# LPCB228_-_TOP.net
KiCad netlist of a schematic drawn in Altium Designer
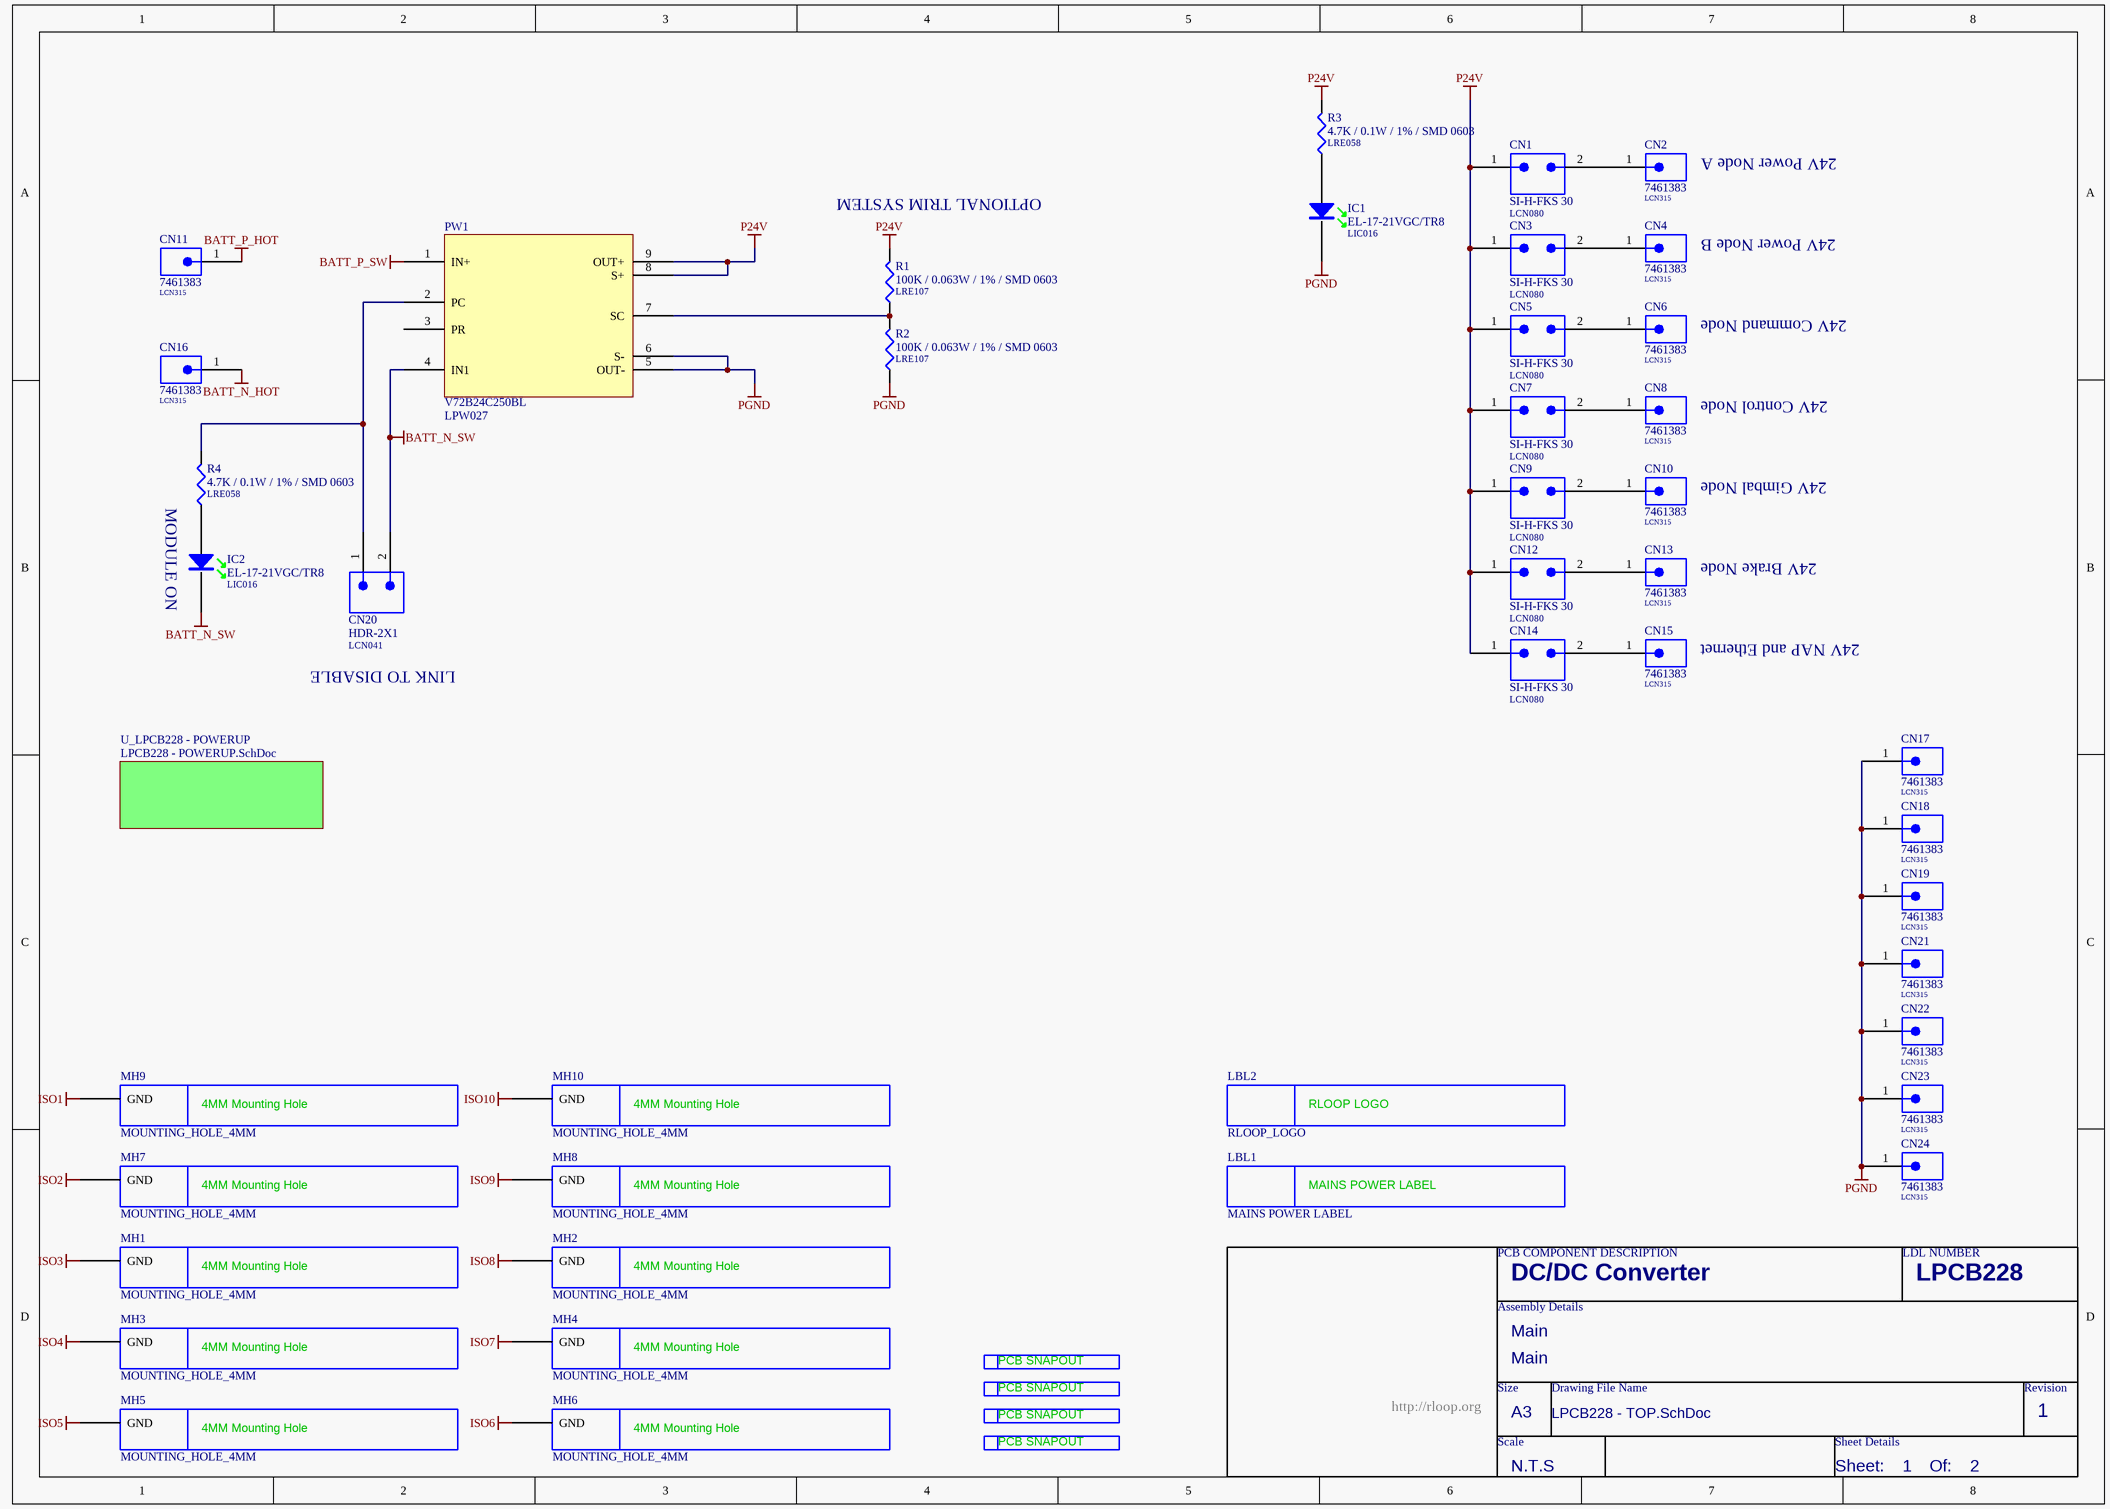
[diagram p0: LPCB228 - TOP.SchDoc]

(export (version "E")
  (design (tool "Eeschema 10.0.6"))
  (components
    (comp (ref "CN1")
      (value "SI-H-FKS 30")
      (footprint "SI-H-FKS-30")
      (description "Connector, Blade Fuse Holder, 5mm Terminals, 30A Max, PTH")
      (fields (field (name "LDL_NUMBER") "LCN080"))
      (libsource (lib "LDL_Connectors") (part "SI-H-FKS 30"))
    )
    (comp (ref "CN2")
      (value "7461383")
      (footprint "7461383")
      (description "Terminal, Bush with M5 Shank")
      (fields (field (name "LDL_NUMBER") "LCN315"))
      (libsource (lib "LDL_Connectors") (part "7461383"))
    )
    (comp (ref "CN3")
      (value "SI-H-FKS 30")
      (footprint "SI-H-FKS-30")
      (description "Connector, Blade Fuse Holder, 5mm Terminals, 30A Max, PTH")
      (fields (field (name "LDL_NUMBER") "LCN080"))
      (libsource (lib "LDL_Connectors") (part "SI-H-FKS 30"))
    )
    (comp (ref "CN4")
      (value "7461383")
      (footprint "7461383")
      (description "Terminal, Bush with M5 Shank")
      (fields (field (name "LDL_NUMBER") "LCN315"))
      (libsource (lib "LDL_Connectors") (part "7461383"))
    )
    (comp (ref "CN5")
      (value "SI-H-FKS 30")
      (footprint "SI-H-FKS-30")
      (description "Connector, Blade Fuse Holder, 5mm Terminals, 30A Max, PTH")
      (fields (field (name "LDL_NUMBER") "LCN080"))
      (libsource (lib "LDL_Connectors") (part "SI-H-FKS 30"))
    )
    (comp (ref "CN6")
      (value "7461383")
      (footprint "7461383")
      (description "Terminal, Bush with M5 Shank")
      (fields (field (name "LDL_NUMBER") "LCN315"))
      (libsource (lib "LDL_Connectors") (part "7461383"))
    )
    (comp (ref "CN7")
      (value "SI-H-FKS 30")
      (footprint "SI-H-FKS-30")
      (description "Connector, Blade Fuse Holder, 5mm Terminals, 30A Max, PTH")
      (fields (field (name "LDL_NUMBER") "LCN080"))
      (libsource (lib "LDL_Connectors") (part "SI-H-FKS 30"))
    )
    (comp (ref "CN8")
      (value "7461383")
      (footprint "7461383")
      (description "Terminal, Bush with M5 Shank")
      (fields (field (name "LDL_NUMBER") "LCN315"))
      (libsource (lib "LDL_Connectors") (part "7461383"))
    )
    (comp (ref "CN9")
      (value "SI-H-FKS 30")
      (footprint "SI-H-FKS-30")
      (description "Connector, Blade Fuse Holder, 5mm Terminals, 30A Max, PTH")
      (fields (field (name "LDL_NUMBER") "LCN080"))
      (libsource (lib "LDL_Connectors") (part "SI-H-FKS 30"))
    )
    (comp (ref "CN10")
      (value "7461383")
      (footprint "7461383")
      (description "Terminal, Bush with M5 Shank")
      (fields (field (name "LDL_NUMBER") "LCN315"))
      (libsource (lib "LDL_Connectors") (part "7461383"))
    )
    (comp (ref "CN11")
      (value "7461383")
      (footprint "7461383")
      (description "Terminal, Bush with M5 Shank")
      (fields (field (name "LDL_NUMBER") "LCN315"))
      (libsource (lib "LDL_Connectors") (part "7461383"))
    )
    (comp (ref "CN12")
      (value "SI-H-FKS 30")
      (footprint "SI-H-FKS-30")
      (description "Connector, Blade Fuse Holder, 5mm Terminals, 30A Max, PTH")
      (fields (field (name "LDL_NUMBER") "LCN080"))
      (libsource (lib "LDL_Connectors") (part "SI-H-FKS 30"))
    )
    (comp (ref "CN13")
      (value "7461383")
      (footprint "7461383")
      (description "Terminal, Bush with M5 Shank")
      (fields (field (name "LDL_NUMBER") "LCN315"))
      (libsource (lib "LDL_Connectors") (part "7461383"))
    )
    (comp (ref "CN14")
      (value "SI-H-FKS 30")
      (footprint "SI-H-FKS-30")
      (description "Connector, Blade Fuse Holder, 5mm Terminals, 30A Max, PTH")
      (fields (field (name "LDL_NUMBER") "LCN080"))
      (libsource (lib "LDL_Connectors") (part "SI-H-FKS 30"))
    )
    (comp (ref "CN15")
      (value "7461383")
      (footprint "7461383")
      (description "Terminal, Bush with M5 Shank")
      (fields (field (name "LDL_NUMBER") "LCN315"))
      (libsource (lib "LDL_Connectors") (part "7461383"))
    )
    (comp (ref "CN16")
      (value "7461383")
      (footprint "7461383")
      (description "Terminal, Bush with M5 Shank")
      (fields (field (name "LDL_NUMBER") "LCN315"))
      (libsource (lib "LDL_Connectors") (part "7461383"))
    )
    (comp (ref "CN17")
      (value "7461383")
      (footprint "7461383")
      (description "Terminal, Bush with M5 Shank")
      (fields (field (name "LDL_NUMBER") "LCN315"))
      (libsource (lib "LDL_Connectors") (part "7461383"))
    )
    (comp (ref "CN18")
      (value "7461383")
      (footprint "7461383")
      (description "Terminal, Bush with M5 Shank")
      (fields (field (name "LDL_NUMBER") "LCN315"))
      (libsource (lib "LDL_Connectors") (part "7461383"))
    )
    (comp (ref "CN19")
      (value "7461383")
      (footprint "7461383")
      (description "Terminal, Bush with M5 Shank")
      (fields (field (name "LDL_NUMBER") "LCN315"))
      (libsource (lib "LDL_Connectors") (part "7461383"))
    )
    (comp (ref "CN20")
      (value "HDR-2X1")
      (footprint "HDR-2X1")
      (description "Header, 2.54mm (0.1in), 2 Pins x 1 Row (40 Per Row In Strip)")
      (fields (field (name "LDL_NUMBER") "LCN041"))
      (libsource (lib "LDL_Connectors") (part "HDR-2X1"))
    )
    (comp (ref "CN21")
      (value "7461383")
      (footprint "7461383")
      (description "Terminal, Bush with M5 Shank")
      (fields (field (name "LDL_NUMBER") "LCN315"))
      (libsource (lib "LDL_Connectors") (part "7461383"))
    )
    (comp (ref "CN22")
      (value "7461383")
      (footprint "7461383")
      (description "Terminal, Bush with M5 Shank")
      (fields (field (name "LDL_NUMBER") "LCN315"))
      (libsource (lib "LDL_Connectors") (part "7461383"))
    )
    (comp (ref "CN23")
      (value "7461383")
      (footprint "7461383")
      (description "Terminal, Bush with M5 Shank")
      (fields (field (name "LDL_NUMBER") "LCN315"))
      (libsource (lib "LDL_Connectors") (part "7461383"))
    )
    (comp (ref "CN24")
      (value "7461383")
      (footprint "7461383")
      (description "Terminal, Bush with M5 Shank")
      (fields (field (name "LDL_NUMBER") "LCN315"))
      (libsource (lib "LDL_Connectors") (part "7461383"))
    )
    (comp (ref "IC1")
      (value "EL-17-21VGC/TR8")
      (footprint "CR2012-0805-LED")
      (description "LED, SMD, 0805 Green [LIC016]")
      (fields (field (name "LDL_NUMBER") "LIC016"))
      (libsource (lib "LDL_Semiconductors") (part "EL-17-21VGC/TR8"))
    )
    (comp (ref "IC2")
      (value "EL-17-21VGC/TR8")
      (footprint "CR2012-0805-LED")
      (description "LED, SMD, 0805 Green [LIC016]")
      (fields (field (name "LDL_NUMBER") "LIC016"))
      (libsource (lib "LDL_Semiconductors") (part "EL-17-21VGC/TR8"))
    )
    (comp (ref "LBL1")
      (value "MAINS POWER LABEL")
      (footprint "MAINS POWER LABEL")
      (libsource (lib "LDL_Mechanical") (part "MAINS POWER LABEL"))
    )
    (comp (ref "LBL2")
      (value "RLOOP_LOGO")
      (footprint "RLOOP_LOGO")
      (libsource (lib "LDL_Mechanical") (part "RLOOP_LOGO"))
    )
    (comp (ref "MH1")
      (value "MOUNTING_HOLE_4MM")
      (footprint "MOUNTING_HOLE_4MM")
      (description "4MM Mouting Hole")
      (libsource (lib "LDL_Mechanical") (part "MOUNTING_HOLE_4MM"))
    )
    (comp (ref "MH2")
      (value "MOUNTING_HOLE_4MM")
      (footprint "MOUNTING_HOLE_4MM")
      (description "4MM Mouting Hole")
      (libsource (lib "LDL_Mechanical") (part "MOUNTING_HOLE_4MM"))
    )
    (comp (ref "MH3")
      (value "MOUNTING_HOLE_4MM")
      (footprint "MOUNTING_HOLE_4MM")
      (description "4MM Mouting Hole")
      (libsource (lib "LDL_Mechanical") (part "MOUNTING_HOLE_4MM"))
    )
    (comp (ref "MH4")
      (value "MOUNTING_HOLE_4MM")
      (footprint "MOUNTING_HOLE_4MM")
      (description "4MM Mouting Hole")
      (libsource (lib "LDL_Mechanical") (part "MOUNTING_HOLE_4MM"))
    )
    (comp (ref "MH5")
      (value "MOUNTING_HOLE_4MM")
      (footprint "MOUNTING_HOLE_4MM")
      (description "4MM Mouting Hole")
      (libsource (lib "LDL_Mechanical") (part "MOUNTING_HOLE_4MM"))
    )
    (comp (ref "MH6")
      (value "MOUNTING_HOLE_4MM")
      (footprint "MOUNTING_HOLE_4MM")
      (description "4MM Mouting Hole")
      (libsource (lib "LDL_Mechanical") (part "MOUNTING_HOLE_4MM"))
    )
    (comp (ref "MH7")
      (value "MOUNTING_HOLE_4MM")
      (footprint "MOUNTING_HOLE_4MM")
      (description "4MM Mouting Hole")
      (libsource (lib "LDL_Mechanical") (part "MOUNTING_HOLE_4MM"))
    )
    (comp (ref "MH8")
      (value "MOUNTING_HOLE_4MM")
      (footprint "MOUNTING_HOLE_4MM")
      (description "4MM Mouting Hole")
      (libsource (lib "LDL_Mechanical") (part "MOUNTING_HOLE_4MM"))
    )
    (comp (ref "MH9")
      (value "MOUNTING_HOLE_4MM")
      (footprint "MOUNTING_HOLE_4MM")
      (description "4MM Mouting Hole")
      (libsource (lib "LDL_Mechanical") (part "MOUNTING_HOLE_4MM"))
    )
    (comp (ref "MH10")
      (value "MOUNTING_HOLE_4MM")
      (footprint "MOUNTING_HOLE_4MM")
      (description "4MM Mouting Hole")
      (libsource (lib "LDL_Mechanical") (part "MOUNTING_HOLE_4MM"))
    )
    (comp (ref "PW1")
      (value "V72B24C250BL")
      (footprint "FASTRAK_MINI_ONBOARD_MOUNT")
      (description "DC-DC Converter, 43-110VIN, 24V, 10A")
      (fields (field (name "LDL_NUMBER") "LPW027"))
      (libsource (lib "LDL_Power") (part "V72B24C250BL"))
    )
    (comp (ref "R1")
      (value "100K / 0.063W / 1% / SMD 0603")
      (footprint "LFP020__CR1608-0603-IPC7351_B")
      (description "Resistor, Ceramic Chip, 100K0, 0.063W, 1%, SMD 0603 [LRE107]")
      (fields (field (name "LDL_NUMBER") "LRE107"))
      (libsource (lib "LDL_Resistors") (part "100K / 0.063W / 1% / SMD 0603"))
    )
    (comp (ref "R2")
      (value "100K / 0.063W / 1% / SMD 0603")
      (footprint "LFP020__CR1608-0603-IPC7351_B")
      (description "Resistor, Ceramic Chip, 100K0, 0.063W, 1%, SMD 0603 [LRE107]")
      (fields (field (name "LDL_NUMBER") "LRE107"))
      (libsource (lib "LDL_Resistors") (part "100K / 0.063W / 1% / SMD 0603"))
    )
    (comp (ref "R3")
      (value "4.7K / 0.1W / 1% / SMD 0603")
      (footprint "LFP020__CR1608-0603-IPC7351_B")
      (description "Resistor, Ceramic Chip, 4K7, 0.1W, 1%, SMD 0603 [LRE058]")
      (fields (field (name "LDL_NUMBER") "LRE058"))
      (libsource (lib "LDL_Resistors") (part "4.7K / 0.1W / 1% / SMD 0603"))
    )
    (comp (ref "R4")
      (value "4.7K / 0.1W / 1% / SMD 0603")
      (footprint "LFP020__CR1608-0603-IPC7351_B")
      (description "Resistor, Ceramic Chip, 4K7, 0.1W, 1%, SMD 0603 [LRE058]")
      (fields (field (name "LDL_NUMBER") "LRE058"))
      (libsource (lib "LDL_Resistors") (part "4.7K / 0.1W / 1% / SMD 0603"))
    )
    (comp (ref "SN1")
      (value "PCB_SNAPOUT")
      (footprint "SNAPOUT_NEW")
      (libsource (lib "LDL_Mechanical") (part "PCB_SNAPOUT"))
    )
    (comp (ref "SN2")
      (value "PCB_SNAPOUT")
      (footprint "SNAPOUT_NEW")
      (libsource (lib "LDL_Mechanical") (part "PCB_SNAPOUT"))
    )
    (comp (ref "SN3")
      (value "PCB_SNAPOUT")
      (footprint "SNAPOUT_NEW")
      (libsource (lib "LDL_Mechanical") (part "PCB_SNAPOUT"))
    )
    (comp (ref "SN4")
      (value "PCB_SNAPOUT")
      (footprint "SNAPOUT_NEW")
      (libsource (lib "LDL_Mechanical") (part "PCB_SNAPOUT"))
    )
  )
  (nets
    (net (code "1") (name "BATT_N_HOT") (class "Default")
      (node (ref "CN16") (pin "1") (pinfunction "1_1") (pintype "passive"))
    )
    (net (code "2") (name "BATT_N_SW") (class "Default")
      (node (ref "CN20") (pin "2") (pinfunction "2_2") (pintype "passive"))
      (node (ref "IC2") (pin "K") (pintype "passive"))
      (node (ref "PW1") (pin "4") (pinfunction "IN1_4") (pintype "passive"))
    )
    (net (code "3") (name "BATT_P_HOT") (class "Default")
      (node (ref "CN11") (pin "1") (pinfunction "1_1") (pintype "passive"))
    )
    (net (code "4") (name "BATT_P_SW") (class "Default")
      (node (ref "PW1") (pin "1") (pinfunction "IN+_1") (pintype "passive"))
    )
    (net (code "5") (name "ISO1") (class "Default")
      (node (ref "MH9") (pin "MOUNT") (pinfunction "GND_MOUNT") (pintype "passive"))
    )
    (net (code "6") (name "ISO2") (class "Default")
      (node (ref "MH7") (pin "MOUNT") (pinfunction "GND_MOUNT") (pintype "passive"))
    )
    (net (code "7") (name "ISO3") (class "Default")
      (node (ref "MH1") (pin "MOUNT") (pinfunction "GND_MOUNT") (pintype "passive"))
    )
    (net (code "8") (name "ISO4") (class "Default")
      (node (ref "MH3") (pin "MOUNT") (pinfunction "GND_MOUNT") (pintype "passive"))
    )
    (net (code "9") (name "ISO5") (class "Default")
      (node (ref "MH5") (pin "MOUNT") (pinfunction "GND_MOUNT") (pintype "passive"))
    )
    (net (code "10") (name "ISO6") (class "Default")
      (node (ref "MH6") (pin "MOUNT") (pinfunction "GND_MOUNT") (pintype "passive"))
    )
    (net (code "11") (name "ISO7") (class "Default")
      (node (ref "MH4") (pin "MOUNT") (pinfunction "GND_MOUNT") (pintype "passive"))
    )
    (net (code "12") (name "ISO8") (class "Default")
      (node (ref "MH2") (pin "MOUNT") (pinfunction "GND_MOUNT") (pintype "passive"))
    )
    (net (code "13") (name "ISO9") (class "Default")
      (node (ref "MH8") (pin "MOUNT") (pinfunction "GND_MOUNT") (pintype "passive"))
    )
    (net (code "14") (name "ISO10") (class "Default")
      (node (ref "MH10") (pin "MOUNT") (pinfunction "GND_MOUNT") (pintype "passive"))
    )
    (net (code "15") (name "Net-(CN1-Pad2)") (class "Default")
      (node (ref "CN1") (pin "2") (pinfunction "2_2") (pintype "passive"))
      (node (ref "CN2") (pin "1") (pinfunction "1_1") (pintype "passive"))
    )
    (net (code "16") (name "Net-(CN3-Pad2)") (class "Default")
      (node (ref "CN3") (pin "2") (pinfunction "2_2") (pintype "passive"))
      (node (ref "CN4") (pin "1") (pinfunction "1_1") (pintype "passive"))
    )
    (net (code "17") (name "Net-(CN5-Pad2)") (class "Default")
      (node (ref "CN5") (pin "2") (pinfunction "2_2") (pintype "passive"))
      (node (ref "CN6") (pin "1") (pinfunction "1_1") (pintype "passive"))
    )
    (net (code "18") (name "Net-(CN7-Pad2)") (class "Default")
      (node (ref "CN7") (pin "2") (pinfunction "2_2") (pintype "passive"))
      (node (ref "CN8") (pin "1") (pinfunction "1_1") (pintype "passive"))
    )
    (net (code "19") (name "Net-(CN10-Pad1)") (class "Default")
      (node (ref "CN10") (pin "1") (pinfunction "1_1") (pintype "passive"))
      (node (ref "CN9") (pin "2") (pinfunction "2_2") (pintype "passive"))
    )
    (net (code "20") (name "Net-(CN12-Pad2)") (class "Default")
      (node (ref "CN12") (pin "2") (pinfunction "2_2") (pintype "passive"))
      (node (ref "CN13") (pin "1") (pinfunction "1_1") (pintype "passive"))
    )
    (net (code "21") (name "Net-(CN14-Pad2)") (class "Default")
      (node (ref "CN14") (pin "2") (pinfunction "2_2") (pintype "passive"))
      (node (ref "CN15") (pin "1") (pinfunction "1_1") (pintype "passive"))
    )
    (net (code "22") (name "Net-(IC1-PadA)") (class "Default")
      (node (ref "IC1") (pin "A") (pintype "passive"))
      (node (ref "R3") (pin "1") (pintype "passive"))
    )
    (net (code "23") (name "Net-(IC2-PadA)") (class "Default")
      (node (ref "IC2") (pin "A") (pintype "passive"))
      (node (ref "R4") (pin "1") (pintype "passive"))
    )
    (net (code "24") (name "Net-(PW1-PC)") (class "Default")
      (node (ref "CN20") (pin "1") (pinfunction "1_1") (pintype "passive"))
      (node (ref "PW1") (pin "2") (pinfunction "PC_2") (pintype "passive"))
      (node (ref "R4") (pin "2") (pintype "passive"))
    )
    (net (code "25") (name "Net-(PW1-SC)") (class "Default")
      (node (ref "PW1") (pin "7") (pinfunction "SC_7") (pintype "passive"))
      (node (ref "R1") (pin "1") (pintype "passive"))
      (node (ref "R2") (pin "2") (pintype "passive"))
    )
    (net (code "26") (name "P24V") (class "Default")
      (node (ref "CN1") (pin "1") (pinfunction "1_1") (pintype "passive"))
      (node (ref "CN12") (pin "1") (pinfunction "1_1") (pintype "passive"))
      (node (ref "CN14") (pin "1") (pinfunction "1_1") (pintype "passive"))
      (node (ref "CN3") (pin "1") (pinfunction "1_1") (pintype "passive"))
      (node (ref "CN5") (pin "1") (pinfunction "1_1") (pintype "passive"))
      (node (ref "CN7") (pin "1") (pinfunction "1_1") (pintype "passive"))
      (node (ref "CN9") (pin "1") (pinfunction "1_1") (pintype "passive"))
      (node (ref "PW1") (pin "8") (pinfunction "S+_8") (pintype "passive"))
      (node (ref "PW1") (pin "9") (pinfunction "OUT+_9") (pintype "passive"))
      (node (ref "R1") (pin "2") (pintype "passive"))
      (node (ref "R3") (pin "2") (pintype "passive"))
    )
    (net (code "27") (name "PGND") (class "Default")
      (node (ref "CN17") (pin "1") (pinfunction "1_1") (pintype "passive"))
      (node (ref "CN18") (pin "1") (pinfunction "1_1") (pintype "passive"))
      (node (ref "CN19") (pin "1") (pinfunction "1_1") (pintype "passive"))
      (node (ref "CN21") (pin "1") (pinfunction "1_1") (pintype "passive"))
      (node (ref "CN22") (pin "1") (pinfunction "1_1") (pintype "passive"))
      (node (ref "CN23") (pin "1") (pinfunction "1_1") (pintype "passive"))
      (node (ref "CN24") (pin "1") (pinfunction "1_1") (pintype "passive"))
      (node (ref "IC1") (pin "K") (pintype "passive"))
      (node (ref "PW1") (pin "5") (pinfunction "OUT-_5") (pintype "passive"))
      (node (ref "PW1") (pin "6") (pinfunction "S-_6") (pintype "passive"))
      (node (ref "R2") (pin "1") (pintype "passive"))
    )
    (net (code "28") (name "unconnected-(PW1-PR-Pad3)") (class "Default")
      (node (ref "PW1") (pin "3") (pinfunction "PR_3") (pintype "passive"))
    )
  )
)
